# Thermostat.net
KiCad netlist of a schematic drawn in EAGLE
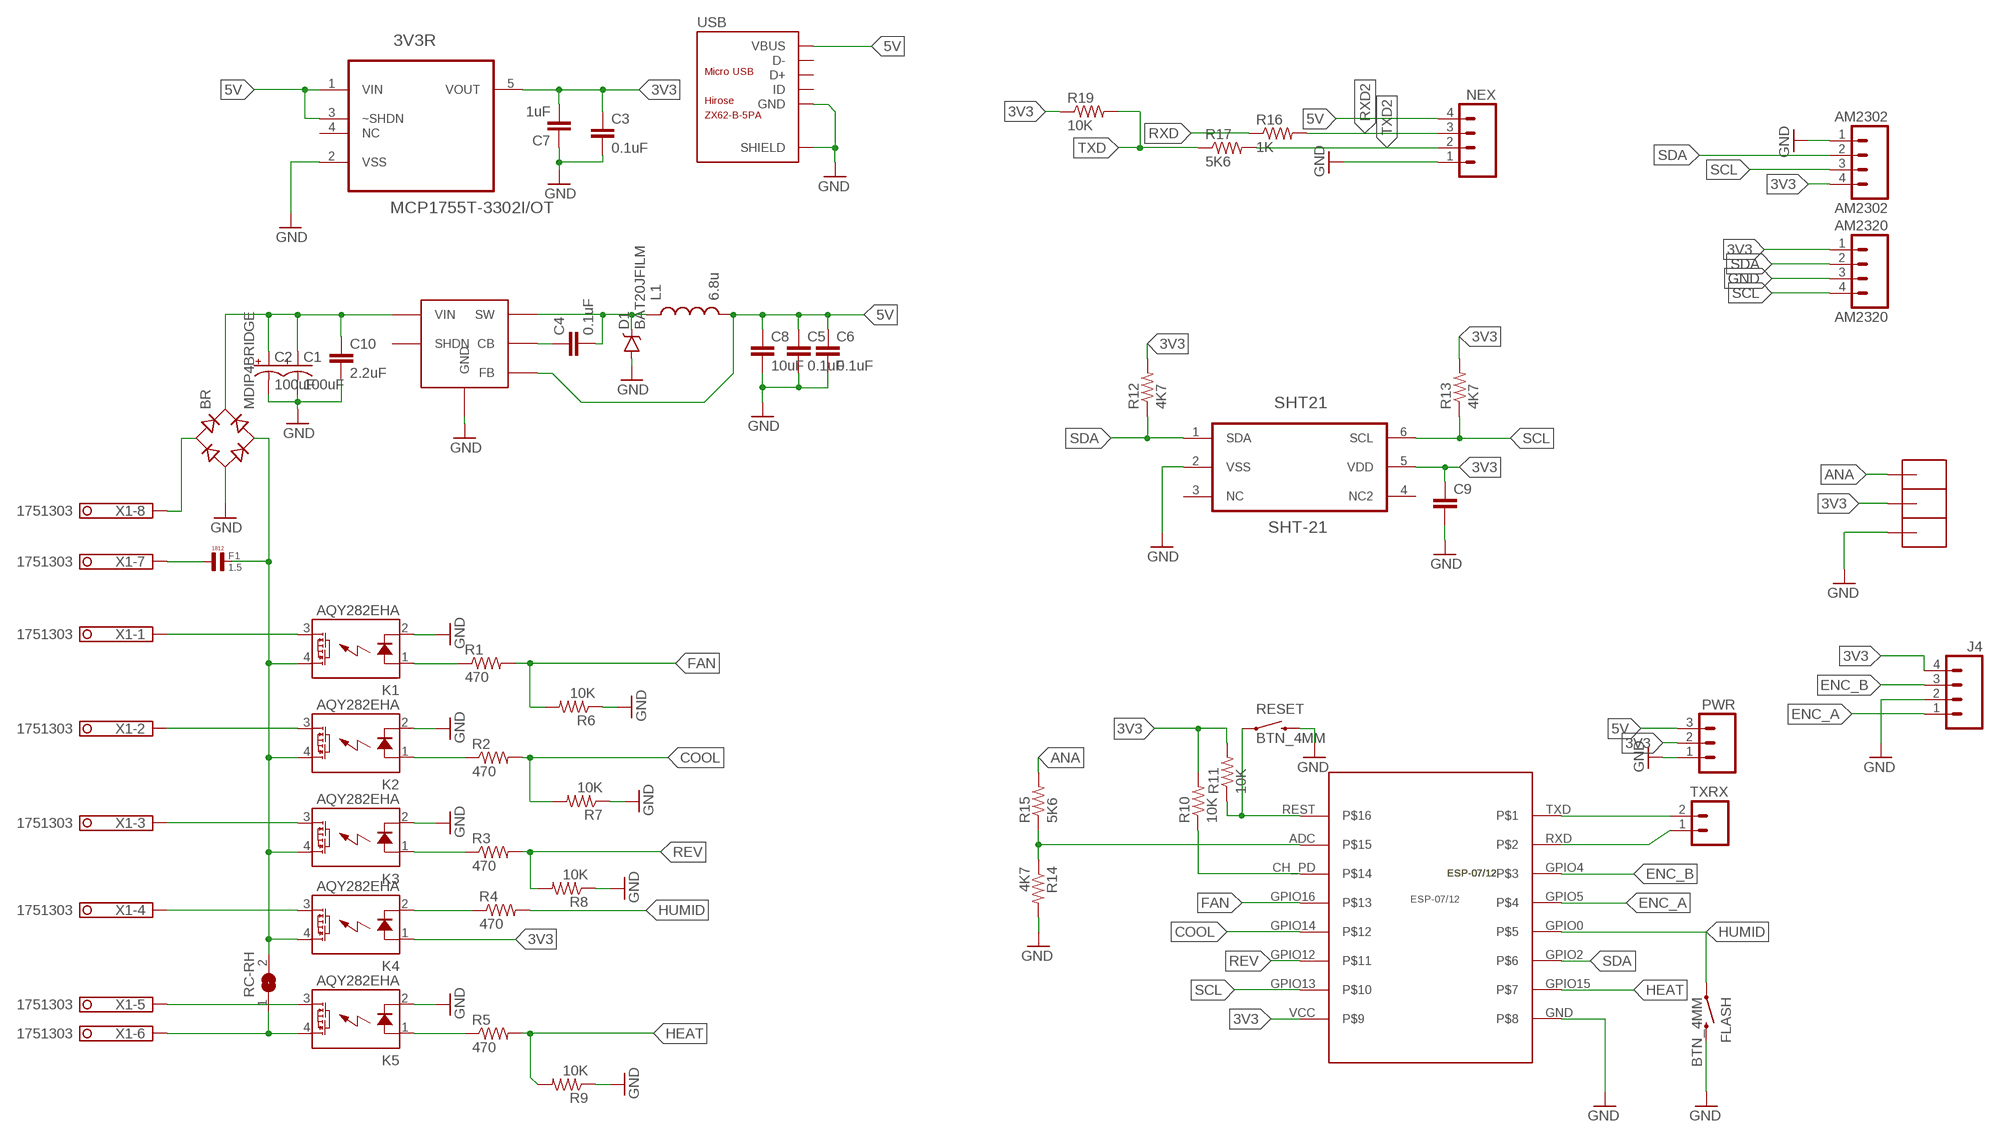
[diagram p0: schematic, sheet 1]

(export (version "E")
  (design (tool "Eeschema 10.0.6"))
  (components
    (comp (ref "3V3R")
      (value "MCP1755T-3302I/OT")
      (footprint "eagle-import:SOT95P270X145-5N")
      (fields (field (name "MPN") "MCP1801T-3302I/OT"))
      (libsource (lib "eagle-import") (part "MCP1801T-3302I/OT"))
    )
    (comp (ref "AM2302")
      (value "AM2302")
      (footprint "eagle-import:1X04")
      (libsource (lib "eagle-import") (part "M04PTH"))
    )
    (comp (ref "AM2320")
      (value "AM2320")
      (footprint "eagle-import:1X04")
      (libsource (lib "eagle-import") (part "M04PTH"))
    )
    (comp (ref "BR")
      (value "MDIP4BRIDGE")
      (footprint "eagle-import:MICRODIP4")
      (libsource (lib "eagle-import") (part "MDIP4BRIDGE"))
    )
    (comp (ref "C1")
      (value "100uF")
      (footprint "eagle-import:PANASONIC_C")
      (libsource (lib "eagle-import") (part "CAP_POLC"))
    )
    (comp (ref "C2")
      (value "100uF")
      (footprint "eagle-import:PANASONIC_C")
      (libsource (lib "eagle-import") (part "CAP_POLC"))
    )
    (comp (ref "C3")
      (value "0.1uF")
      (footprint "eagle-import:0805")
      (libsource (lib "eagle-import") (part "CAP0805"))
    )
    (comp (ref "C4")
      (value "0.1uF")
      (footprint "eagle-import:0805")
      (libsource (lib "eagle-import") (part "CAP0805"))
    )
    (comp (ref "C5")
      (value "0.1uF")
      (footprint "eagle-import:0805")
      (libsource (lib "eagle-import") (part "CAP0805"))
    )
    (comp (ref "C6")
      (value "0.1uF")
      (footprint "eagle-import:0805")
      (libsource (lib "eagle-import") (part "CAP0805"))
    )
    (comp (ref "C7")
      (value "1uF")
      (footprint "eagle-import:0805")
      (libsource (lib "eagle-import") (part "CAP0805"))
    )
    (comp (ref "C8")
      (value "10uF")
      (footprint "eagle-import:0805")
      (libsource (lib "eagle-import") (part "CAP0805"))
    )
    (comp (ref "C9")
      (value "CAP0603-CAP")
      (footprint "eagle-import:0603-CAP")
      (libsource (lib "eagle-import") (part "CAP0603-CAP"))
    )
    (comp (ref "C10")
      (value "2.2uF")
      (footprint "eagle-import:0805")
      (libsource (lib "eagle-import") (part "CAP0805"))
    )
    (comp (ref "D1")
      (value "BAT20JFILM")
      (footprint "eagle-import:SOD-323")
      (libsource (lib "eagle-import") (part "BAT20JFILM"))
    )
    (comp (ref "F1")
      (value "1.5")
      (footprint "eagle-import:L4,8")
      (libsource (lib "eagle-import") (part "0,1µF"))
    )
    (comp (ref "FLASH")
      (value "BTN_4MM")
      (footprint "eagle-import:BTN_4MM")
      (libsource (lib "eagle-import") (part "BTN_4MM"))
    )
    (comp (ref "J4")
      (value "M04PTH")
      (footprint "eagle-import:1X04")
      (libsource (lib "eagle-import") (part "M04PTH"))
    )
    (comp (ref "K1")
      (value "AQY282EHA")
      (footprint "eagle-import:SOP04")
      (libsource (lib "eagle-import") (part "AQYSOP22"))
    )
    (comp (ref "K2")
      (value "AQY282EHA")
      (footprint "eagle-import:SOP04")
      (libsource (lib "eagle-import") (part "AQYSOP22"))
    )
    (comp (ref "K3")
      (value "AQY282EHA")
      (footprint "eagle-import:SOP04")
      (libsource (lib "eagle-import") (part "AQYSOP22"))
    )
    (comp (ref "K4")
      (value "AQY282EHA")
      (footprint "eagle-import:SOP04")
      (libsource (lib "eagle-import") (part "AQYSOP22"))
    )
    (comp (ref "K5")
      (value "AQY282EHA")
      (footprint "eagle-import:SOP04")
      (libsource (lib "eagle-import") (part "AQYSOP22"))
    )
    (comp (ref "L1")
      (value "6.8u")
      (footprint "eagle-import:1007")
      (libsource (lib "eagle-import") (part "INDUCTOR1007"))
    )
    (comp (ref "NEX")
      (value "M04PTH")
      (footprint "eagle-import:1X04")
      (libsource (lib "eagle-import") (part "M04PTH"))
    )
    (comp (ref "PWR")
      (value "M03PTH")
      (footprint "eagle-import:1X03")
      (libsource (lib "eagle-import") (part "M03PTH"))
    )
    (comp (ref "R1")
      (value "470")
      (footprint "eagle-import:0805")
      (libsource (lib "eagle-import") (part "RESISTOR0805-RES"))
    )
    (comp (ref "R2")
      (value "470")
      (footprint "eagle-import:0805")
      (libsource (lib "eagle-import") (part "RESISTOR0805-RES"))
    )
    (comp (ref "R3")
      (value "470")
      (footprint "eagle-import:0805")
      (libsource (lib "eagle-import") (part "RESISTOR0805-RES"))
    )
    (comp (ref "R4")
      (value "470")
      (footprint "eagle-import:0805")
      (libsource (lib "eagle-import") (part "RESISTOR0805-RES"))
    )
    (comp (ref "R5")
      (value "470")
      (footprint "eagle-import:0805")
      (libsource (lib "eagle-import") (part "RESISTOR0805-RES"))
    )
    (comp (ref "R6")
      (value "10K")
      (footprint "eagle-import:0805")
      (libsource (lib "eagle-import") (part "RESISTOR0805-RES"))
    )
    (comp (ref "R7")
      (value "10K")
      (footprint "eagle-import:0805")
      (libsource (lib "eagle-import") (part "RESISTOR0805-RES"))
    )
    (comp (ref "R8")
      (value "10K")
      (footprint "eagle-import:0805")
      (libsource (lib "eagle-import") (part "RESISTOR0805-RES"))
    )
    (comp (ref "R9")
      (value "10K")
      (footprint "eagle-import:0805")
      (libsource (lib "eagle-import") (part "RESISTOR0805-RES"))
    )
    (comp (ref "R10")
      (value "10K")
      (footprint "eagle-import:0805")
      (libsource (lib "eagle-import") (part "SparkFun-Resistors_RESISTOR0805-RES"))
    )
    (comp (ref "R11")
      (value "10K")
      (footprint "eagle-import:0805")
      (libsource (lib "eagle-import") (part "SparkFun-Resistors_RESISTOR0805-RES"))
    )
    (comp (ref "R12")
      (value "4K7")
      (footprint "eagle-import:0805")
      (libsource (lib "eagle-import") (part "SparkFun-Resistors_RESISTOR0805-RES"))
    )
    (comp (ref "R13")
      (value "4K7")
      (footprint "eagle-import:0805")
      (libsource (lib "eagle-import") (part "SparkFun-Resistors_RESISTOR0805-RES"))
    )
    (comp (ref "R14")
      (value "4K7")
      (footprint "eagle-import:0805")
      (libsource (lib "eagle-import") (part "SparkFun-Resistors_RESISTOR0805-RES"))
    )
    (comp (ref "R15")
      (value "5K6")
      (footprint "eagle-import:0805")
      (libsource (lib "eagle-import") (part "SparkFun-Resistors_RESISTOR0805-RES"))
    )
    (comp (ref "R16")
      (value "1K")
      (footprint "eagle-import:0805")
      (libsource (lib "eagle-import") (part "SparkFun-Resistors_RESISTOR0805-RES"))
    )
    (comp (ref "R17")
      (value "5K6")
      (footprint "eagle-import:0805")
      (libsource (lib "eagle-import") (part "SparkFun-Resistors_RESISTOR0805-RES"))
    )
    (comp (ref "R19")
      (value "10K")
      (footprint "eagle-import:0805")
      (libsource (lib "eagle-import") (part "SparkFun-Resistors_RESISTOR0805-RES"))
    )
    (comp (ref "RC-RH")
      (value "SJ")
      (footprint "eagle-import:SJ")
      (libsource (lib "eagle-import") (part "SJ"))
    )
    (comp (ref "RESET")
      (value "BTN_4MM")
      (footprint "eagle-import:BTN_4MM")
      (libsource (lib "eagle-import") (part "BTN_4MM"))
    )
    (comp (ref "SHT21")
      (value "SHT-21")
      (footprint "eagle-import:SHT21")
      (libsource (lib "eagle-import") (part "SHT-21"))
    )
    (comp (ref "TXRX")
      (value "M02PTH")
      (footprint "eagle-import:1X02")
      (libsource (lib "eagle-import") (part "M02PTH"))
    )
    (comp (ref "U$1")
      (value "ESP-07/12")
      (footprint "eagle-import:ESP-07_12")
      (libsource (lib "eagle-import") (part "ESP-07/12"))
    )
    (comp (ref "U$2")
      (value "SMD-PAD182X64")
      (footprint "eagle-import:SMD-PAD1")
      (libsource (lib "eagle-import") (part "SMD-PAD182X64"))
    )
    (comp (ref "U$3")
      (value "SMD-PAD182X64")
      (footprint "eagle-import:SMD-PAD1")
      (libsource (lib "eagle-import") (part "SMD-PAD182X64"))
    )
    (comp (ref "U$4")
      (value "SMD-PAD182X64")
      (footprint "eagle-import:SMD-PAD1")
      (libsource (lib "eagle-import") (part "SMD-PAD182X64"))
    )
    (comp (ref "USB")
      (value "ZX62-B-5PA")
      (footprint "eagle-import:MICRO-USB5+6P-SMD-0.65-AB")
      (libsource (lib "eagle-import") (part "MICRO-USB-SMD(ZX62-B-5PA)"))
    )
    (comp (ref "VREG")
      (value "LMR16006YQ")
      (footprint "eagle-import:SOT-23-6")
      (libsource (lib "eagle-import") (part "LMR16006YQ"))
    )
    (comp (ref "X1")
      (value "1751303")
      (footprint "eagle-import:1751303")
      (libsource (lib "eagle-import") (part "1751303"))
    )
  )
  (nets
    (net (code "1") (name "/NC") (class "Default")
      (node (ref "SHT21") (pin "3") (pinfunction "NC_3") (pintype "power_in"))
    )
    (net (code "2") (name "3V3") (class "Default")
      (node (ref "3V3R") (pin "5") (pinfunction "VOUT_5") (pintype "output"))
      (node (ref "AM2302") (pin "4") (pinfunction "4_4") (pintype "passive"))
      (node (ref "AM2320") (pin "1") (pinfunction "1_1") (pintype "passive"))
      (node (ref "C3") (pin "1") (pinfunction "1_1") (pintype "passive"))
      (node (ref "C7") (pin "2") (pinfunction "2_2") (pintype "passive"))
      (node (ref "C9") (pin "1") (pinfunction "1_1") (pintype "passive"))
      (node (ref "J4") (pin "4") (pinfunction "4_4") (pintype "passive"))
      (node (ref "K4") (pin "1") (pinfunction "A_1") (pintype "passive"))
      (node (ref "PWR") (pin "2") (pinfunction "2_2") (pintype "passive"))
      (node (ref "R10") (pin "2") (pinfunction "2_2") (pintype "passive"))
      (node (ref "R11") (pin "2") (pinfunction "2_2") (pintype "passive"))
      (node (ref "R12") (pin "2") (pinfunction "2_2") (pintype "passive"))
      (node (ref "R13") (pin "2") (pinfunction "2_2") (pintype "passive"))
      (node (ref "R19") (pin "1") (pinfunction "1_1") (pintype "passive"))
      (node (ref "SHT21") (pin "5") (pinfunction "VDD_5") (pintype "bidirectional"))
      (node (ref "U$1") (pin "VCC") (pinfunction "P$9_VCC") (pintype "bidirectional"))
      (node (ref "U$3") (pin ">PAD") (pinfunction "P$1_>PAD") (pintype "bidirectional"))
    )
    (net (code "3") (name "5V") (class "Default")
      (node (ref "3V3R") (pin "1") (pinfunction "VIN_1") (pintype "power_in"))
      (node (ref "3V3R") (pin "3") (pinfunction "~{SHDN}_3") (pintype "input"))
      (node (ref "C5") (pin "1") (pinfunction "1_1") (pintype "passive"))
      (node (ref "C6") (pin "1") (pinfunction "1_1") (pintype "passive"))
      (node (ref "C8") (pin "1") (pinfunction "1_1") (pintype "passive"))
      (node (ref "L1") (pin "2") (pinfunction "2_2") (pintype "passive"))
      (node (ref "NEX") (pin "4") (pinfunction "4_4") (pintype "passive"))
      (node (ref "PWR") (pin "3") (pinfunction "3_3") (pintype "passive"))
      (node (ref "USB") (pin "1") (pinfunction "VBUS_1") (pintype "power_in"))
      (node (ref "VREG") (pin "3") (pinfunction "FB_3") (pintype "input"))
    )
    (net (code "4") (name "ANA") (class "Default")
      (node (ref "R15") (pin "2") (pinfunction "2_2") (pintype "passive"))
      (node (ref "U$4") (pin ">PAD") (pinfunction "P$1_>PAD") (pintype "bidirectional"))
    )
    (net (code "5") (name "COOL") (class "Default")
      (node (ref "R2") (pin "2") (pinfunction "2_2") (pintype "passive"))
      (node (ref "R7") (pin "2") (pinfunction "2_2") (pintype "passive"))
      (node (ref "U$1") (pin "GPIO14") (pinfunction "P$12_GPIO14") (pintype "bidirectional"))
    )
    (net (code "6") (name "ENC_A") (class "Default")
      (node (ref "J4") (pin "1") (pinfunction "1_1") (pintype "passive"))
      (node (ref "U$1") (pin "GPIO5") (pinfunction "P$4_GPIO5") (pintype "bidirectional"))
    )
    (net (code "7") (name "ENC_B") (class "Default")
      (node (ref "J4") (pin "3") (pinfunction "3_3") (pintype "passive"))
      (node (ref "U$1") (pin "GPIO4") (pinfunction "P$3_GPIO4") (pintype "bidirectional"))
    )
    (net (code "8") (name "FAN") (class "Default")
      (node (ref "R1") (pin "2") (pinfunction "2_2") (pintype "passive"))
      (node (ref "R6") (pin "2") (pinfunction "2_2") (pintype "passive"))
      (node (ref "U$1") (pin "GPIO16") (pinfunction "P$13_GPIO16") (pintype "bidirectional"))
    )
    (net (code "9") (name "GND") (class "Default")
      (node (ref "3V3R") (pin "2") (pinfunction "VSS_2") (pintype "passive"))
      (node (ref "AM2302") (pin "1") (pinfunction "1_1") (pintype "passive"))
      (node (ref "AM2320") (pin "3") (pinfunction "3_3") (pintype "passive"))
      (node (ref "BR") (pin "-") (pinfunction "-_-") (pintype "passive"))
      (node (ref "C1") (pin "-") (pinfunction "-_-") (pintype "passive"))
      (node (ref "C10") (pin "2") (pinfunction "2_2") (pintype "passive"))
      (node (ref "C2") (pin "-") (pinfunction "-_-") (pintype "passive"))
      (node (ref "C3") (pin "2") (pinfunction "2_2") (pintype "passive"))
      (node (ref "C5") (pin "2") (pinfunction "2_2") (pintype "passive"))
      (node (ref "C6") (pin "2") (pinfunction "2_2") (pintype "passive"))
      (node (ref "C7") (pin "1") (pinfunction "1_1") (pintype "passive"))
      (node (ref "C8") (pin "2") (pinfunction "2_2") (pintype "passive"))
      (node (ref "C9") (pin "2") (pinfunction "2_2") (pintype "passive"))
      (node (ref "D1") (pin "A") (pinfunction "A_A") (pintype "passive"))
      (node (ref "FLASH") (pin "2") (pinfunction "2_2") (pintype "passive"))
      (node (ref "J4") (pin "2") (pinfunction "2_2") (pintype "passive"))
      (node (ref "K1") (pin "2") (pinfunction "K_2") (pintype "passive"))
      (node (ref "K2") (pin "2") (pinfunction "K_2") (pintype "passive"))
      (node (ref "K3") (pin "2") (pinfunction "K_2") (pintype "passive"))
      (node (ref "K5") (pin "2") (pinfunction "K_2") (pintype "passive"))
      (node (ref "NEX") (pin "1") (pinfunction "1_1") (pintype "passive"))
      (node (ref "PWR") (pin "1") (pinfunction "1_1") (pintype "passive"))
      (node (ref "R14") (pin "2") (pinfunction "2_2") (pintype "passive"))
      (node (ref "R6") (pin "1") (pinfunction "1_1") (pintype "passive"))
      (node (ref "R7") (pin "1") (pinfunction "1_1") (pintype "passive"))
      (node (ref "R8") (pin "1") (pinfunction "1_1") (pintype "passive"))
      (node (ref "R9") (pin "1") (pinfunction "1_1") (pintype "passive"))
      (node (ref "RESET") (pin "2") (pinfunction "2_2") (pintype "passive"))
      (node (ref "SHT21") (pin "2") (pinfunction "VSS_2") (pintype "input"))
      (node (ref "U$1") (pin "GND") (pinfunction "P$8_GND") (pintype "bidirectional"))
      (node (ref "U$2") (pin ">PAD") (pinfunction "P$1_>PAD") (pintype "bidirectional"))
      (node (ref "USB") (pin "5") (pinfunction "GND_5") (pintype "power_in"))
      (node (ref "USB") (pin "P1") (pinfunction "SHIELD_P1") (pintype "power_in"))
      (node (ref "USB") (pin "P2") (pinfunction "SHIELD_P2") (pintype "power_in"))
      (node (ref "USB") (pin "P3") (pinfunction "SHIELD_P3") (pintype "power_in"))
      (node (ref "USB") (pin "P4") (pinfunction "SHIELD_P4") (pintype "power_in"))
      (node (ref "USB") (pin "P5") (pinfunction "SHIELD_P5") (pintype "power_in"))
      (node (ref "USB") (pin "P6") (pinfunction "SHIELD_P6") (pintype "power_in"))
      (node (ref "VREG") (pin "2") (pinfunction "GND_2") (pintype "input"))
    )
    (net (code "10") (name "HEAT") (class "Default")
      (node (ref "R5") (pin "2") (pinfunction "2_2") (pintype "passive"))
      (node (ref "R9") (pin "2") (pinfunction "2_2") (pintype "passive"))
      (node (ref "U$1") (pin "GPIO15") (pinfunction "P$7_GPIO15") (pintype "bidirectional"))
    )
    (net (code "11") (name "HUMID") (class "Default")
      (node (ref "FLASH") (pin "1") (pinfunction "1_1") (pintype "passive"))
      (node (ref "R4") (pin "2") (pinfunction "2_2") (pintype "passive"))
      (node (ref "U$1") (pin "GPIO0") (pinfunction "P$5_GPIO0") (pintype "bidirectional"))
    )
    (net (code "12") (name "Net-(F1-1)") (class "Default")
      (node (ref "F1") (pin "P$1") (pinfunction "1_P$1") (pintype "passive"))
      (node (ref "X1") (pin "7") (pinfunction "K_7") (pintype "passive"))
    )
    (net (code "13") (name "Net-(F1-2)") (class "Default")
      (node (ref "BR") (pin "AC2") (pinfunction "AC2_AC2") (pintype "passive"))
      (node (ref "F1") (pin "P$2") (pinfunction "2_P$2") (pintype "passive"))
      (node (ref "K1") (pin "4") (pinfunction "DS1_4") (pintype "passive"))
      (node (ref "K2") (pin "4") (pinfunction "DS1_4") (pintype "passive"))
      (node (ref "K3") (pin "4") (pinfunction "DS1_4") (pintype "passive"))
      (node (ref "K4") (pin "4") (pinfunction "DS1_4") (pintype "passive"))
      (node (ref "RC-RH") (pin "2") (pinfunction "2_2") (pintype "passive"))
    )
    (net (code "14") (name "Net-(K1-A)") (class "Default")
      (node (ref "K1") (pin "1") (pinfunction "A_1") (pintype "passive"))
      (node (ref "R1") (pin "1") (pinfunction "1_1") (pintype "passive"))
    )
    (net (code "15") (name "Net-(K1-DS2)") (class "Default")
      (node (ref "K1") (pin "3") (pinfunction "DS2_3") (pintype "passive"))
      (node (ref "X1") (pin "1") (pinfunction "K_1") (pintype "passive"))
    )
    (net (code "16") (name "Net-(K2-A)") (class "Default")
      (node (ref "K2") (pin "1") (pinfunction "A_1") (pintype "passive"))
      (node (ref "R2") (pin "1") (pinfunction "1_1") (pintype "passive"))
    )
    (net (code "17") (name "Net-(K2-DS2)") (class "Default")
      (node (ref "K2") (pin "3") (pinfunction "DS2_3") (pintype "passive"))
      (node (ref "X1") (pin "2") (pinfunction "K_2") (pintype "passive"))
    )
    (net (code "18") (name "Net-(K3-A)") (class "Default")
      (node (ref "K3") (pin "1") (pinfunction "A_1") (pintype "passive"))
      (node (ref "R3") (pin "1") (pinfunction "1_1") (pintype "passive"))
    )
    (net (code "19") (name "Net-(K3-DS2)") (class "Default")
      (node (ref "K3") (pin "3") (pinfunction "DS2_3") (pintype "passive"))
      (node (ref "X1") (pin "3") (pinfunction "K_3") (pintype "passive"))
    )
    (net (code "20") (name "Net-(K4-DS2)") (class "Default")
      (node (ref "K4") (pin "3") (pinfunction "DS2_3") (pintype "passive"))
      (node (ref "X1") (pin "4") (pinfunction "K_4") (pintype "passive"))
    )
    (net (code "21") (name "Net-(K4-K)") (class "Default")
      (node (ref "K4") (pin "2") (pinfunction "K_2") (pintype "passive"))
      (node (ref "R4") (pin "1") (pinfunction "1_1") (pintype "passive"))
    )
    (net (code "22") (name "Net-(K5-A)") (class "Default")
      (node (ref "K5") (pin "1") (pinfunction "A_1") (pintype "passive"))
      (node (ref "R5") (pin "1") (pinfunction "1_1") (pintype "passive"))
    )
    (net (code "23") (name "Net-(K5-DS1)") (class "Default")
      (node (ref "K5") (pin "4") (pinfunction "DS1_4") (pintype "passive"))
      (node (ref "RC-RH") (pin "1") (pinfunction "1_1") (pintype "passive"))
      (node (ref "X1") (pin "6") (pinfunction "K_6") (pintype "passive"))
    )
    (net (code "24") (name "Net-(K5-DS2)") (class "Default")
      (node (ref "K5") (pin "3") (pinfunction "DS2_3") (pintype "passive"))
      (node (ref "X1") (pin "5") (pinfunction "K_5") (pintype "passive"))
    )
    (net (code "25") (name "Net-(U$1-P$14)") (class "Default")
      (node (ref "R10") (pin "1") (pinfunction "1_1") (pintype "passive"))
      (node (ref "U$1") (pin "CH_PD") (pinfunction "P$14_CH_PD") (pintype "bidirectional"))
    )
    (net (code "26") (name "Net-(U$1-P$15)") (class "Default")
      (node (ref "R14") (pin "1") (pinfunction "1_1") (pintype "passive"))
      (node (ref "R15") (pin "1") (pinfunction "1_1") (pintype "passive"))
      (node (ref "U$1") (pin "ADC") (pinfunction "P$15_ADC") (pintype "bidirectional"))
    )
    (net (code "27") (name "Net-(U$1-P$16)") (class "Default")
      (node (ref "R11") (pin "1") (pinfunction "1_1") (pintype "passive"))
      (node (ref "RESET") (pin "1") (pinfunction "1_1") (pintype "passive"))
      (node (ref "U$1") (pin "REST") (pinfunction "P$16_REST") (pintype "bidirectional"))
    )
    (net (code "28") (name "Net-(VREG-CB)") (class "Default")
      (node (ref "C4") (pin "1") (pinfunction "1_1") (pintype "passive"))
      (node (ref "VREG") (pin "1") (pinfunction "CB_1") (pintype "input"))
    )
    (net (code "29") (name "Net-(VREG-SW)") (class "Default")
      (node (ref "C4") (pin "2") (pinfunction "2_2") (pintype "passive"))
      (node (ref "D1") (pin "C") (pinfunction "C_C") (pintype "passive"))
      (node (ref "L1") (pin "1") (pinfunction "1_1") (pintype "passive"))
      (node (ref "VREG") (pin "6") (pinfunction "SW_6") (pintype "output"))
    )
    (net (code "30") (name "Net-(VREG-VIN)") (class "Default")
      (node (ref "BR") (pin "+") (pinfunction "+_+") (pintype "passive"))
      (node (ref "C1") (pin "+") (pinfunction "+_+") (pintype "passive"))
      (node (ref "C10") (pin "1") (pinfunction "1_1") (pintype "passive"))
      (node (ref "C2") (pin "+") (pinfunction "+_+") (pintype "passive"))
      (node (ref "VREG") (pin "5") (pinfunction "VIN_5") (pintype "input"))
    )
    (net (code "31") (name "Net-(X1H-K)") (class "Default")
      (node (ref "BR") (pin "AC1") (pinfunction "AC1_AC1") (pintype "passive"))
      (node (ref "X1") (pin "8") (pinfunction "K_8") (pintype "passive"))
    )
    (net (code "32") (name "REV") (class "Default")
      (node (ref "R3") (pin "2") (pinfunction "2_2") (pintype "passive"))
      (node (ref "R8") (pin "2") (pinfunction "2_2") (pintype "passive"))
      (node (ref "U$1") (pin "GPIO12") (pinfunction "P$11_GPIO12") (pintype "bidirectional"))
    )
    (net (code "33") (name "RXD") (class "Default")
      (node (ref "R16") (pin "1") (pinfunction "1_1") (pintype "passive"))
      (node (ref "TXRX") (pin "1") (pinfunction "1_1") (pintype "passive"))
      (node (ref "U$1") (pin "RXD") (pinfunction "P$2_RXD") (pintype "bidirectional"))
    )
    (net (code "34") (name "RXD2") (class "Default")
      (node (ref "NEX") (pin "3") (pinfunction "3_3") (pintype "passive"))
      (node (ref "R16") (pin "2") (pinfunction "2_2") (pintype "passive"))
    )
    (net (code "35") (name "SCL") (class "Default")
      (node (ref "AM2302") (pin "3") (pinfunction "3_3") (pintype "passive"))
      (node (ref "AM2320") (pin "4") (pinfunction "4_4") (pintype "passive"))
      (node (ref "R13") (pin "1") (pinfunction "1_1") (pintype "passive"))
      (node (ref "SHT21") (pin "6") (pinfunction "SCL_6") (pintype "bidirectional"))
      (node (ref "U$1") (pin "GPIO13") (pinfunction "P$10_GPIO13") (pintype "bidirectional"))
    )
    (net (code "36") (name "SDA") (class "Default")
      (node (ref "AM2302") (pin "2") (pinfunction "2_2") (pintype "passive"))
      (node (ref "AM2320") (pin "2") (pinfunction "2_2") (pintype "passive"))
      (node (ref "R12") (pin "1") (pinfunction "1_1") (pintype "passive"))
      (node (ref "SHT21") (pin "1") (pinfunction "SDA_1") (pintype "power_in"))
      (node (ref "U$1") (pin "GPIO2") (pinfunction "P$6_GPIO2") (pintype "bidirectional"))
    )
    (net (code "37") (name "TXD") (class "Default")
      (node (ref "R17") (pin "1") (pinfunction "1_1") (pintype "passive"))
      (node (ref "R19") (pin "2") (pinfunction "2_2") (pintype "passive"))
      (node (ref "TXRX") (pin "2") (pinfunction "2_2") (pintype "passive"))
      (node (ref "U$1") (pin "TXD") (pinfunction "P$1_TXD") (pintype "bidirectional"))
    )
    (net (code "38") (name "TXD2") (class "Default")
      (node (ref "NEX") (pin "2") (pinfunction "2_2") (pintype "passive"))
      (node (ref "R17") (pin "2") (pinfunction "2_2") (pintype "passive"))
    )
    (net (code "39") (name "unconnected-(3V3R-NC-Pad4)") (class "Default")
      (node (ref "3V3R") (pin "4") (pinfunction "NC_4") (pintype "no_connect"))
    )
    (net (code "40") (name "unconnected-(SHT21-NC2-Pad4)") (class "Default")
      (node (ref "SHT21") (pin "4") (pinfunction "NC2_4") (pintype "bidirectional"))
    )
    (net (code "41") (name "unconnected-(USB-D+-Pad3)") (class "Default")
      (node (ref "USB") (pin "3") (pinfunction "D+_3") (pintype "bidirectional"))
    )
    (net (code "42") (name "unconnected-(USB-D--Pad2)") (class "Default")
      (node (ref "USB") (pin "2") (pinfunction "D-_2") (pintype "bidirectional"))
    )
    (net (code "43") (name "unconnected-(USB-ID-Pad4)") (class "Default")
      (node (ref "USB") (pin "4") (pinfunction "ID_4") (pintype "bidirectional"))
    )
    (net (code "44") (name "unconnected-(VREG-SHDN-Pad4)") (class "Default")
      (node (ref "VREG") (pin "4") (pinfunction "SHDN_4") (pintype "input"))
    )
  )
)
